# T08-TxClicker-Rev1a.net
KiCad netlist of a schematic drawn in EAGLE
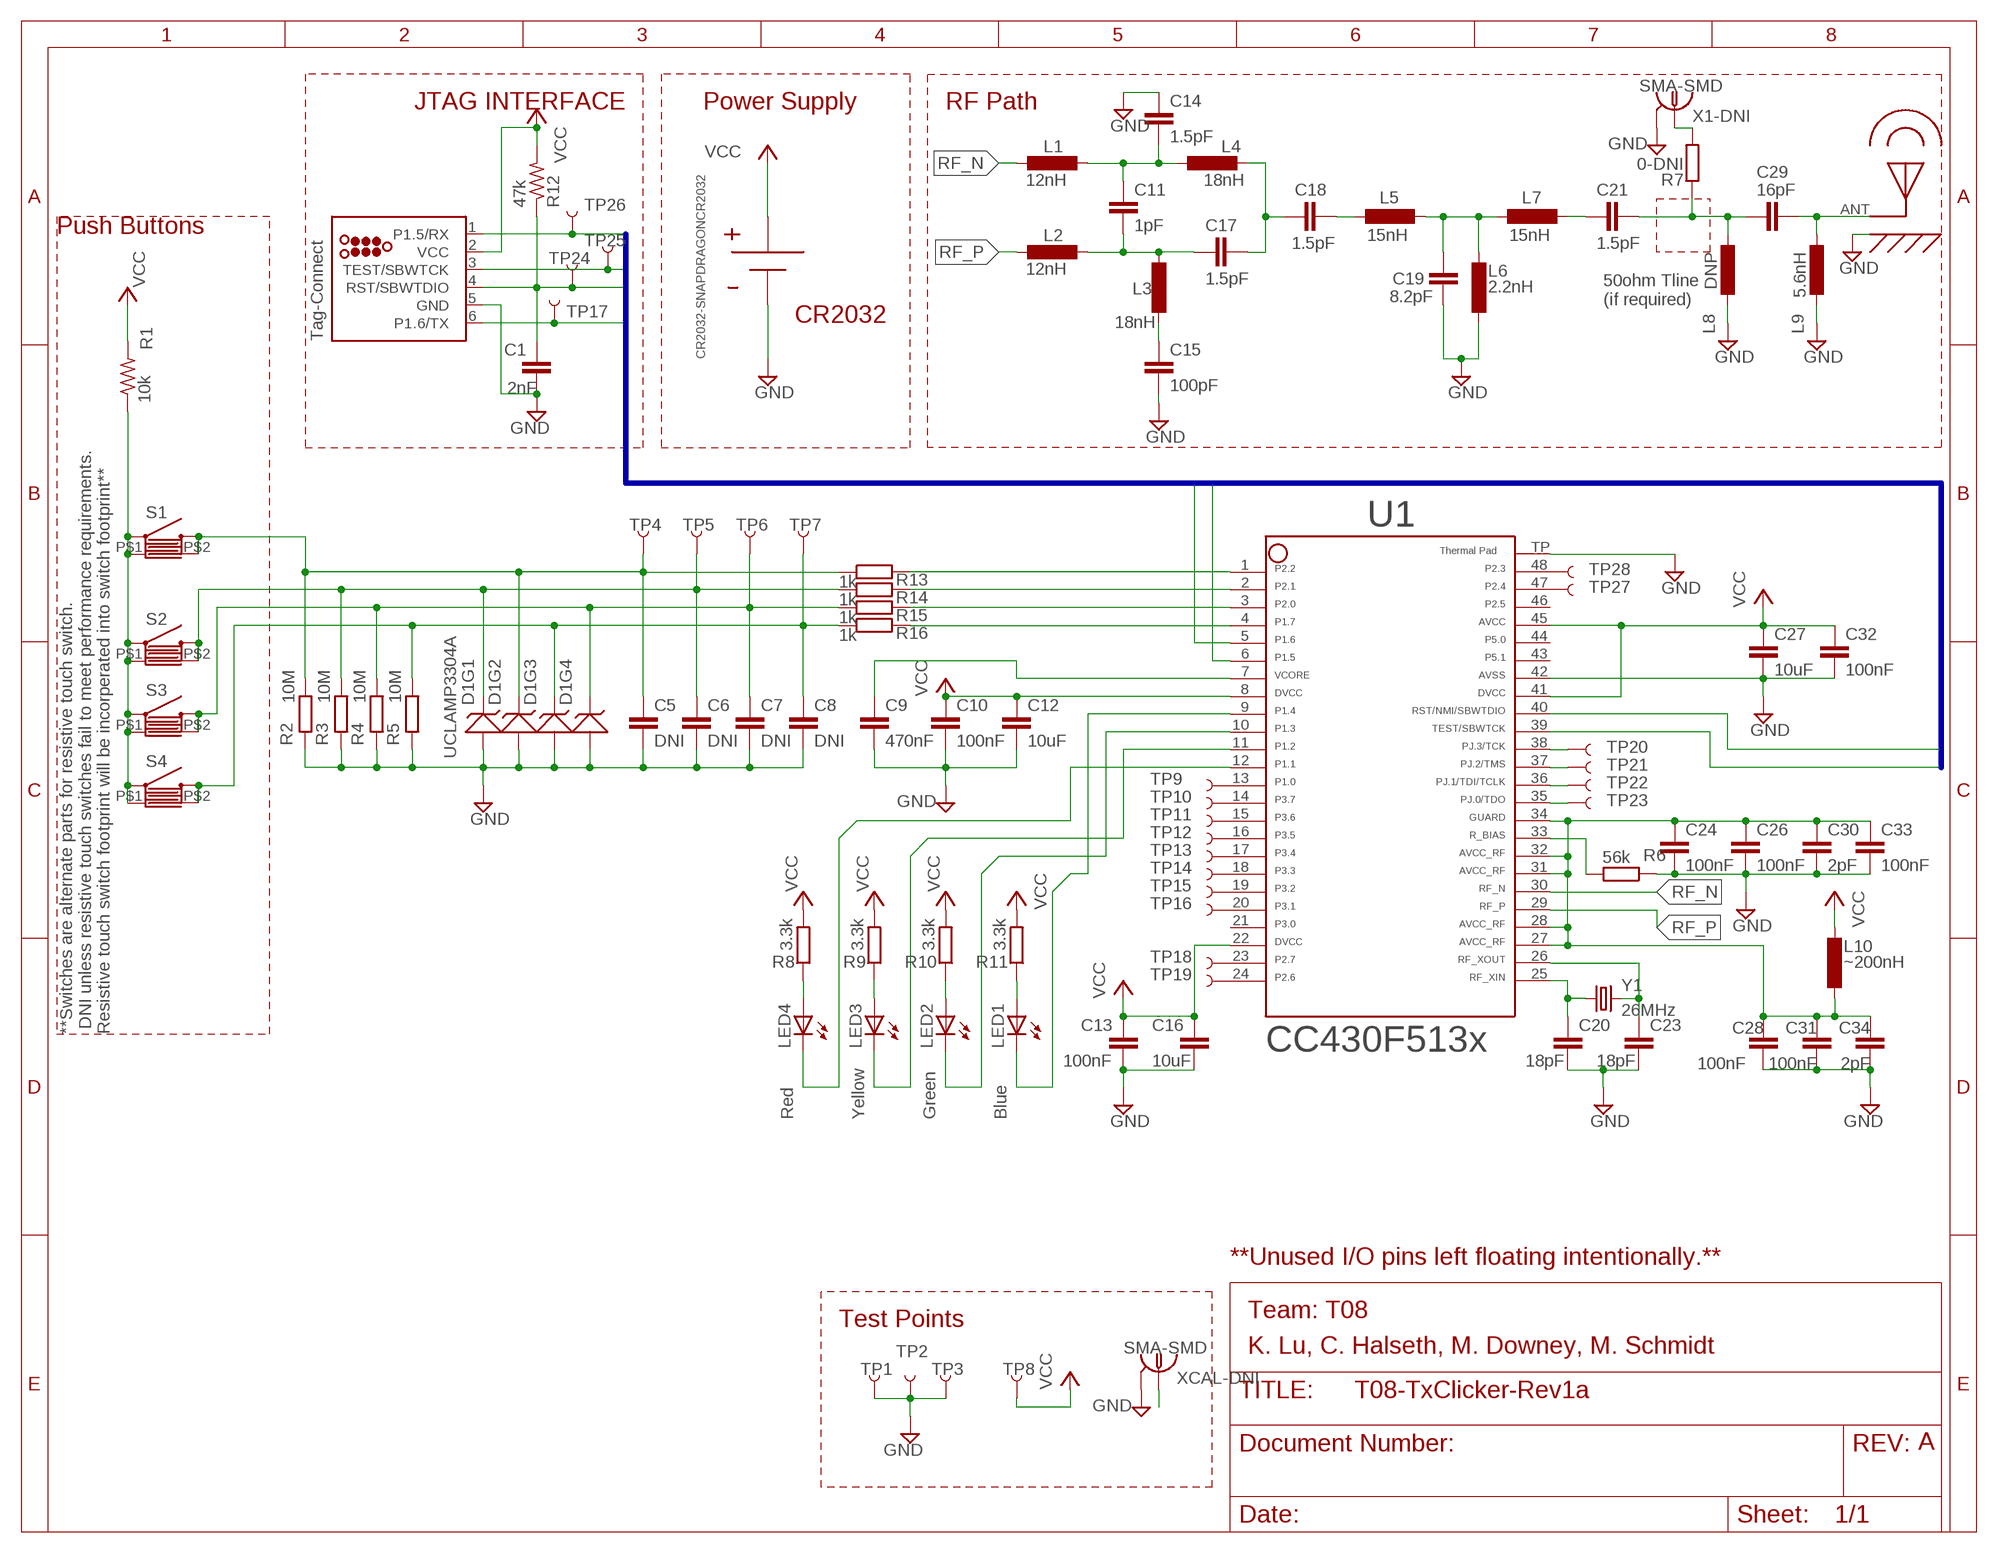
[diagram p0: schematic, sheet 1]

(export (version "E")
  (design (tool "Eeschema 10.0.6"))
  (components
    (comp (ref "C1")
      (value "2nF")
      (footprint "eagle-import:C0603")
      (libsource (lib "eagle-import") (part "C0603"))
    )
    (comp (ref "C5")
      (value "DNI")
      (footprint "eagle-import:C0603")
      (libsource (lib "eagle-import") (part "C0603"))
    )
    (comp (ref "C6")
      (value "DNI")
      (footprint "eagle-import:C0603")
      (libsource (lib "eagle-import") (part "C0603"))
    )
    (comp (ref "C7")
      (value "DNI")
      (footprint "eagle-import:C0603")
      (libsource (lib "eagle-import") (part "C0603"))
    )
    (comp (ref "C8")
      (value "DNI")
      (footprint "eagle-import:C0603")
      (libsource (lib "eagle-import") (part "C0603"))
    )
    (comp (ref "C9")
      (value "470nF")
      (footprint "eagle-import:C0603")
      (libsource (lib "eagle-import") (part "C0603"))
    )
    (comp (ref "C10")
      (value "100nF")
      (footprint "eagle-import:C0603")
      (libsource (lib "eagle-import") (part "C0603"))
    )
    (comp (ref "C11")
      (value "1pF")
      (footprint "eagle-import:C0402")
      (libsource (lib "eagle-import") (part "C0402"))
    )
    (comp (ref "C12")
      (value "10uF")
      (footprint "eagle-import:C0603")
      (libsource (lib "eagle-import") (part "C0603"))
    )
    (comp (ref "C13")
      (value "100nF")
      (footprint "eagle-import:C0603")
      (libsource (lib "eagle-import") (part "C0603"))
    )
    (comp (ref "C14")
      (value "1.5pF")
      (footprint "eagle-import:C0402")
      (libsource (lib "eagle-import") (part "C0402"))
    )
    (comp (ref "C15")
      (value "100pF")
      (footprint "eagle-import:C0402")
      (libsource (lib "eagle-import") (part "C0402"))
    )
    (comp (ref "C16")
      (value "10uF")
      (footprint "eagle-import:C0603")
      (libsource (lib "eagle-import") (part "C0603"))
    )
    (comp (ref "C17")
      (value "1.5pF")
      (footprint "eagle-import:C0402")
      (libsource (lib "eagle-import") (part "C0402"))
    )
    (comp (ref "C18")
      (value "1.5pF")
      (footprint "eagle-import:C0402")
      (libsource (lib "eagle-import") (part "C0402"))
    )
    (comp (ref "C19")
      (value "8.2pF")
      (footprint "eagle-import:C0402")
      (libsource (lib "eagle-import") (part "C0402"))
    )
    (comp (ref "C20")
      (value "18pF")
      (footprint "eagle-import:C0603")
      (libsource (lib "eagle-import") (part "C0603"))
    )
    (comp (ref "C21")
      (value "1.5pF")
      (footprint "eagle-import:C0402")
      (libsource (lib "eagle-import") (part "C0402"))
    )
    (comp (ref "C23")
      (value "18pF")
      (footprint "eagle-import:C0603")
      (libsource (lib "eagle-import") (part "C0603"))
    )
    (comp (ref "C24")
      (value "100nF")
      (footprint "eagle-import:C0603")
      (libsource (lib "eagle-import") (part "C0603"))
    )
    (comp (ref "C26")
      (value "100nF")
      (footprint "eagle-import:C0603")
      (libsource (lib "eagle-import") (part "C0603"))
    )
    (comp (ref "C27")
      (value "10uF")
      (footprint "eagle-import:C0603")
      (libsource (lib "eagle-import") (part "C0603"))
    )
    (comp (ref "C28")
      (value "100nF")
      (footprint "eagle-import:C0603")
      (libsource (lib "eagle-import") (part "C0603"))
    )
    (comp (ref "C29")
      (value "16pF")
      (footprint "eagle-import:C0402")
      (libsource (lib "eagle-import") (part "C0402"))
    )
    (comp (ref "C30")
      (value "2pF")
      (footprint "eagle-import:C0603")
      (libsource (lib "eagle-import") (part "C0603"))
    )
    (comp (ref "C31")
      (value "100nF")
      (footprint "eagle-import:C0603")
      (libsource (lib "eagle-import") (part "C0603"))
    )
    (comp (ref "C32")
      (value "100nF")
      (footprint "eagle-import:C0603")
      (libsource (lib "eagle-import") (part "C0603"))
    )
    (comp (ref "C33")
      (value "100nF")
      (footprint "eagle-import:C0603")
      (libsource (lib "eagle-import") (part "C0603"))
    )
    (comp (ref "C34")
      (value "2pF")
      (footprint "eagle-import:C0603")
      (libsource (lib "eagle-import") (part "C0603"))
    )
    (comp (ref "D1")
      (value "UCLAMP3304A")
      (footprint "eagle-import:SOT666")
      (libsource (lib "eagle-import") (part "UCLAMP3304A"))
    )
    (comp (ref "L1")
      (value "12nH")
      (footprint "eagle-import:L0402")
      (libsource (lib "eagle-import") (part "LL0402"))
    )
    (comp (ref "L2")
      (value "12nH")
      (footprint "eagle-import:L0402")
      (libsource (lib "eagle-import") (part "LL0402"))
    )
    (comp (ref "L3")
      (value "18nH")
      (footprint "eagle-import:L0402")
      (libsource (lib "eagle-import") (part "LL0402"))
    )
    (comp (ref "L4")
      (value "18nH")
      (footprint "eagle-import:L0402")
      (libsource (lib "eagle-import") (part "LL0402"))
    )
    (comp (ref "L5")
      (value "15nH")
      (footprint "eagle-import:L0402")
      (libsource (lib "eagle-import") (part "LL0402"))
    )
    (comp (ref "L6")
      (value "2.2nH")
      (footprint "eagle-import:L0402")
      (libsource (lib "eagle-import") (part "LL0402"))
    )
    (comp (ref "L7")
      (value "15nH")
      (footprint "eagle-import:L0402")
      (libsource (lib "eagle-import") (part "LL0402"))
    )
    (comp (ref "L8")
      (value "DNP")
      (footprint "eagle-import:L0402")
      (libsource (lib "eagle-import") (part "LL0402"))
    )
    (comp (ref "L9")
      (value "5.6nH")
      (footprint "eagle-import:L0402")
      (libsource (lib "eagle-import") (part "LL0402"))
    )
    (comp (ref "L10")
      (value "~200nH")
      (footprint "eagle-import:L0603")
      (libsource (lib "eagle-import") (part "LL0603"))
    )
    (comp (ref "LED1")
      (value "Blue")
      (footprint "eagle-import:CHIP-LED0603")
      (libsource (lib "eagle-import") (part "LEDCHIP-LED0603"))
    )
    (comp (ref "LED2")
      (value "Green")
      (footprint "eagle-import:CHIP-LED0603")
      (libsource (lib "eagle-import") (part "LEDCHIP-LED0603"))
    )
    (comp (ref "LED3")
      (value "Yellow")
      (footprint "eagle-import:CHIP-LED0603")
      (libsource (lib "eagle-import") (part "LEDCHIP-LED0603"))
    )
    (comp (ref "LED4")
      (value "Red")
      (footprint "eagle-import:CHIP-LED0603")
      (libsource (lib "eagle-import") (part "LEDCHIP-LED0603"))
    )
    (comp (ref "R1")
      (value "10k")
      (footprint "eagle-import:R0603")
      (libsource (lib "eagle-import") (part "R-US_R0603"))
    )
    (comp (ref "R2")
      (value "10M")
      (footprint "eagle-import:R0603")
      (libsource (lib "eagle-import") (part "R0603"))
    )
    (comp (ref "R3")
      (value "10M")
      (footprint "eagle-import:R0603")
      (libsource (lib "eagle-import") (part "R0603"))
    )
    (comp (ref "R4")
      (value "10M")
      (footprint "eagle-import:R0603")
      (libsource (lib "eagle-import") (part "R0603"))
    )
    (comp (ref "R5")
      (value "10M")
      (footprint "eagle-import:R0603")
      (libsource (lib "eagle-import") (part "R0603"))
    )
    (comp (ref "R6")
      (value "56k")
      (footprint "eagle-import:R0603")
      (libsource (lib "eagle-import") (part "R0603"))
    )
    (comp (ref "R7")
      (value "0-DNI")
      (footprint "eagle-import:R0603")
      (libsource (lib "eagle-import") (part "R0603"))
    )
    (comp (ref "R8")
      (value "3.3k")
      (footprint "eagle-import:R0603")
      (libsource (lib "eagle-import") (part "R0603"))
    )
    (comp (ref "R9")
      (value "3.3k")
      (footprint "eagle-import:R0603")
      (libsource (lib "eagle-import") (part "R0603"))
    )
    (comp (ref "R10")
      (value "3.3k")
      (footprint "eagle-import:R0603")
      (libsource (lib "eagle-import") (part "R0603"))
    )
    (comp (ref "R11")
      (value "3.3k")
      (footprint "eagle-import:R0603")
      (libsource (lib "eagle-import") (part "R0603"))
    )
    (comp (ref "R12")
      (value "47k")
      (footprint "eagle-import:R0603")
      (libsource (lib "eagle-import") (part "R-US_R0603"))
    )
    (comp (ref "R13")
      (value "1k")
      (footprint "eagle-import:R0603")
      (libsource (lib "eagle-import") (part "R0603"))
    )
    (comp (ref "R14")
      (value "1k")
      (footprint "eagle-import:R0603")
      (libsource (lib "eagle-import") (part "R0603"))
    )
    (comp (ref "R15")
      (value "1k")
      (footprint "eagle-import:R0603")
      (libsource (lib "eagle-import") (part "R0603"))
    )
    (comp (ref "R16")
      (value "1k")
      (footprint "eagle-import:R0603")
      (libsource (lib "eagle-import") (part "R0603"))
    )
    (comp (ref "S1")
      (value "TOUCHPAD_SWITCH_COMBOSWITC_TOUCHPAD")
      (footprint "eagle-import:TACTILE-PTH-12MM")
      (libsource (lib "eagle-import") (part "TOUCHPAD_SWITCH_COMBOSWITC_TOUCHPAD"))
    )
    (comp (ref "S2")
      (value "TOUCHPAD_SWITCH_COMBOSWITC_TOUCHPAD")
      (footprint "eagle-import:TACTILE-PTH-12MM")
      (libsource (lib "eagle-import") (part "TOUCHPAD_SWITCH_COMBOSWITC_TOUCHPAD"))
    )
    (comp (ref "S3")
      (value "TOUCHPAD_SWITCH_COMBOSWITC_TOUCHPAD")
      (footprint "eagle-import:TACTILE-PTH-12MM")
      (libsource (lib "eagle-import") (part "TOUCHPAD_SWITCH_COMBOSWITC_TOUCHPAD"))
    )
    (comp (ref "S4")
      (value "TOUCHPAD_SWITCH_COMBOSWITC_TOUCHPAD")
      (footprint "eagle-import:TACTILE-PTH-12MM")
      (libsource (lib "eagle-import") (part "TOUCHPAD_SWITCH_COMBOSWITC_TOUCHPAD"))
    )
    (comp (ref "TP1")
      (value "TEST-POINT3")
      (footprint "eagle-import:PAD.03X.03")
      (libsource (lib "eagle-import") (part "TEST-POINT3"))
    )
    (comp (ref "TP2")
      (value "TEST-POINT3")
      (footprint "eagle-import:PAD.03X.03")
      (libsource (lib "eagle-import") (part "TEST-POINT3"))
    )
    (comp (ref "TP3")
      (value "TEST-POINT3")
      (footprint "eagle-import:PAD.03X.03")
      (libsource (lib "eagle-import") (part "TEST-POINT3"))
    )
    (comp (ref "TP4")
      (value "TEST-POINT3")
      (footprint "eagle-import:PAD.03X.03")
      (libsource (lib "eagle-import") (part "TEST-POINT3"))
    )
    (comp (ref "TP5")
      (value "TEST-POINT3")
      (footprint "eagle-import:PAD.03X.03")
      (libsource (lib "eagle-import") (part "TEST-POINT3"))
    )
    (comp (ref "TP6")
      (value "TEST-POINT3")
      (footprint "eagle-import:PAD.03X.03")
      (libsource (lib "eagle-import") (part "TEST-POINT3"))
    )
    (comp (ref "TP7")
      (value "TEST-POINT3")
      (footprint "eagle-import:PAD.03X.03")
      (libsource (lib "eagle-import") (part "TEST-POINT3"))
    )
    (comp (ref "TP8")
      (value "TEST-POINT3")
      (footprint "eagle-import:PAD.03X.03")
      (libsource (lib "eagle-import") (part "TEST-POINT3"))
    )
    (comp (ref "TP9")
      (value "TP9")
      (footprint "eagle-import:PAD.03X.03")
      (libsource (lib "eagle-import") (part "TEST-POINT3"))
    )
    (comp (ref "TP10")
      (value "TEST-POINT3")
      (footprint "eagle-import:PAD.03X.03")
      (libsource (lib "eagle-import") (part "TEST-POINT3"))
    )
    (comp (ref "TP11")
      (value "TEST-POINT3")
      (footprint "eagle-import:PAD.03X.03")
      (libsource (lib "eagle-import") (part "TEST-POINT3"))
    )
    (comp (ref "TP12")
      (value "TEST-POINT3")
      (footprint "eagle-import:PAD.03X.03")
      (libsource (lib "eagle-import") (part "TEST-POINT3"))
    )
    (comp (ref "TP13")
      (value "TEST-POINT3")
      (footprint "eagle-import:PAD.03X.03")
      (libsource (lib "eagle-import") (part "TEST-POINT3"))
    )
    (comp (ref "TP14")
      (value "TEST-POINT3")
      (footprint "eagle-import:PAD.03X.03")
      (libsource (lib "eagle-import") (part "TEST-POINT3"))
    )
    (comp (ref "TP15")
      (value "TEST-POINT3")
      (footprint "eagle-import:PAD.03X.03")
      (libsource (lib "eagle-import") (part "TEST-POINT3"))
    )
    (comp (ref "TP16")
      (value "TEST-POINT3")
      (footprint "eagle-import:PAD.03X.03")
      (libsource (lib "eagle-import") (part "TEST-POINT3"))
    )
    (comp (ref "TP17")
      (value "TEST-POINT3")
      (footprint "eagle-import:PAD.03X.03")
      (libsource (lib "eagle-import") (part "TEST-POINT3"))
    )
    (comp (ref "TP18")
      (value "TEST-POINT3")
      (footprint "eagle-import:PAD.03X.03")
      (libsource (lib "eagle-import") (part "TEST-POINT3"))
    )
    (comp (ref "TP19")
      (value "TEST-POINT3")
      (footprint "eagle-import:PAD.03X.03")
      (libsource (lib "eagle-import") (part "TEST-POINT3"))
    )
    (comp (ref "TP20")
      (value "TEST-POINT3")
      (footprint "eagle-import:PAD.03X.03")
      (libsource (lib "eagle-import") (part "TEST-POINT3"))
    )
    (comp (ref "TP21")
      (value "TEST-POINT3")
      (footprint "eagle-import:PAD.03X.03")
      (libsource (lib "eagle-import") (part "TEST-POINT3"))
    )
    (comp (ref "TP22")
      (value "TEST-POINT3")
      (footprint "eagle-import:PAD.03X.03")
      (libsource (lib "eagle-import") (part "TEST-POINT3"))
    )
    (comp (ref "TP23")
      (value "TEST-POINT3")
      (footprint "eagle-import:PAD.03X.03")
      (libsource (lib "eagle-import") (part "TEST-POINT3"))
    )
    (comp (ref "TP24")
      (value "TEST-POINT3")
      (footprint "eagle-import:PAD.03X.03")
      (libsource (lib "eagle-import") (part "TEST-POINT3"))
    )
    (comp (ref "TP25")
      (value "TEST-POINT3")
      (footprint "eagle-import:PAD.03X.03")
      (libsource (lib "eagle-import") (part "TEST-POINT3"))
    )
    (comp (ref "TP26")
      (value "TEST-POINT3")
      (footprint "eagle-import:PAD.03X.03")
      (libsource (lib "eagle-import") (part "TEST-POINT3"))
    )
    (comp (ref "TP27")
      (value "TEST-POINT3")
      (footprint "eagle-import:PAD.03X.03")
      (libsource (lib "eagle-import") (part "TEST-POINT3"))
    )
    (comp (ref "TP28")
      (value "TEST-POINT3")
      (footprint "eagle-import:PAD.03X.03")
      (libsource (lib "eagle-import") (part "TEST-POINT3"))
    )
    (comp (ref "U$1")
      (value "TC2030-MCP")
      (footprint "eagle-import:TC2030-MCP")
      (libsource (lib "eagle-import") (part "TC2030-MCP"))
    )
    (comp (ref "U$5")
      (value "CR2032-SNAPDRAGONCR2032")
      (footprint "eagle-import:CR2032-SNAPDRAGON")
      (libsource (lib "eagle-import") (part "CR2032-SNAPDRAGONCR2032"))
    )
    (comp (ref "U$6")
      (value "PCB_ANTENNA_915MHZOSHP")
      (footprint "eagle-import:PCB_ANTENNA_915MHZ")
      (libsource (lib "eagle-import") (part "PCB_ANTENNA_915MHZOSHP"))
    )
    (comp (ref "U1")
      (value "CC430F513X---RGZ48")
      (footprint "eagle-import:RGZ48")
      (libsource (lib "eagle-import") (part "CC430F513X---RGZ48"))
    )
    (comp (ref "X1-DNI")
      (value "SMA-SMD")
      (footprint "eagle-import:SMA-SMD")
      (libsource (lib "eagle-import") (part "SMA-SMD"))
    )
    (comp (ref "XCAL-DNI")
      (value "SMA-SMD")
      (footprint "eagle-import:SMA-SMD")
      (libsource (lib "eagle-import") (part "SMA-SMD"))
    )
    (comp (ref "Y1")
      (value "26MHz")
      (footprint "eagle-import:CRYSTAL-TXC-7A")
      (libsource (lib "eagle-import") (part "CRYSTALTXC-7A"))
    )
  )
  (nets
    (net (code "1") (name "/P1.5{slash}RX") (class "Default")
      (node (ref "TP26") (pin "P$1") (pinfunction "1_P$1") (pintype "bidirectional"))
      (node (ref "U$1") (pin "1") (pinfunction "P1.5/RX_1") (pintype "bidirectional"))
      (node (ref "U1") (pin "6") (pinfunction "6_6") (pintype "bidirectional"))
    )
    (net (code "2") (name "/P1.6{slash}TX") (class "Default")
      (node (ref "TP17") (pin "P$1") (pinfunction "1_P$1") (pintype "bidirectional"))
      (node (ref "U$1") (pin "6") (pinfunction "P1.6/TX_6") (pintype "bidirectional"))
      (node (ref "U1") (pin "5") (pinfunction "5_5") (pintype "bidirectional"))
    )
    (net (code "3") (name "/RST{slash}NMI{slash}SBWTDIO") (class "Default")
      (node (ref "C1") (pin "1") (pinfunction "1_1") (pintype "passive"))
      (node (ref "R12") (pin "1") (pinfunction "1_1") (pintype "passive"))
      (node (ref "TP24") (pin "P$1") (pinfunction "1_P$1") (pintype "bidirectional"))
      (node (ref "U$1") (pin "4") (pinfunction "RST/SBWTDIO_4") (pintype "bidirectional"))
      (node (ref "U1") (pin "40") (pinfunction "40_40") (pintype "bidirectional"))
    )
    (net (code "4") (name "/TEST{slash}SBWTCK") (class "Default")
      (node (ref "TP25") (pin "P$1") (pinfunction "1_P$1") (pintype "bidirectional"))
      (node (ref "U$1") (pin "3") (pinfunction "TEST/SBWTCK_3") (pintype "bidirectional"))
      (node (ref "U1") (pin "39") (pinfunction "39_39") (pintype "input"))
    )
    (net (code "5") (name "GND") (class "Default")
      (node (ref "C1") (pin "2") (pinfunction "2_2") (pintype "passive"))
      (node (ref "C10") (pin "2") (pinfunction "2_2") (pintype "passive"))
      (node (ref "C12") (pin "2") (pinfunction "2_2") (pintype "passive"))
      (node (ref "C13") (pin "2") (pinfunction "2_2") (pintype "passive"))
      (node (ref "C14") (pin "P$1") (pinfunction "1_P$1") (pintype "passive"))
      (node (ref "C15") (pin "P$2") (pinfunction "2_P$2") (pintype "passive"))
      (node (ref "C16") (pin "2") (pinfunction "2_2") (pintype "passive"))
      (node (ref "C19") (pin "P$1") (pinfunction "1_P$1") (pintype "passive"))
      (node (ref "C20") (pin "2") (pinfunction "2_2") (pintype "passive"))
      (node (ref "C23") (pin "2") (pinfunction "2_2") (pintype "passive"))
      (node (ref "C24") (pin "2") (pinfunction "2_2") (pintype "passive"))
      (node (ref "C26") (pin "2") (pinfunction "2_2") (pintype "passive"))
      (node (ref "C27") (pin "2") (pinfunction "2_2") (pintype "passive"))
      (node (ref "C28") (pin "2") (pinfunction "2_2") (pintype "passive"))
      (node (ref "C30") (pin "2") (pinfunction "2_2") (pintype "passive"))
      (node (ref "C31") (pin "2") (pinfunction "2_2") (pintype "passive"))
      (node (ref "C32") (pin "2") (pinfunction "2_2") (pintype "passive"))
      (node (ref "C33") (pin "2") (pinfunction "2_2") (pintype "passive"))
      (node (ref "C34") (pin "2") (pinfunction "2_2") (pintype "passive"))
      (node (ref "C5") (pin "2") (pinfunction "2_2") (pintype "passive"))
      (node (ref "C6") (pin "2") (pinfunction "2_2") (pintype "passive"))
      (node (ref "C7") (pin "2") (pinfunction "2_2") (pintype "passive"))
      (node (ref "C8") (pin "2") (pinfunction "2_2") (pintype "passive"))
      (node (ref "C9") (pin "2") (pinfunction "2_2") (pintype "passive"))
      (node (ref "D1") (pin "2") (pinfunction "2_2") (pintype "bidirectional"))
      (node (ref "D1") (pin "5") (pinfunction "2_5") (pintype "bidirectional"))
      (node (ref "L6") (pin "P$2") (pinfunction "2_P$2") (pintype "passive"))
      (node (ref "L8") (pin "P$1") (pinfunction "1_P$1") (pintype "passive"))
      (node (ref "L9") (pin "P$1") (pinfunction "1_P$1") (pintype "passive"))
      (node (ref "R2") (pin "1") (pinfunction "1_1") (pintype "passive"))
      (node (ref "R3") (pin "1") (pinfunction "1_1") (pintype "passive"))
      (node (ref "R4") (pin "1") (pinfunction "1_1") (pintype "passive"))
      (node (ref "R5") (pin "1") (pinfunction "1_1") (pintype "passive"))
      (node (ref "R6") (pin "1") (pinfunction "1_1") (pintype "passive"))
      (node (ref "TP1") (pin "P$1") (pinfunction "1_P$1") (pintype "bidirectional"))
      (node (ref "TP2") (pin "P$1") (pinfunction "1_P$1") (pintype "bidirectional"))
      (node (ref "TP3") (pin "P$1") (pinfunction "1_P$1") (pintype "bidirectional"))
      (node (ref "U$1") (pin "5") (pinfunction "GND_5") (pintype "power_in"))
      (node (ref "U$5") (pin "V-") (pinfunction "V-_V-") (pintype "bidirectional"))
      (node (ref "U$6") (pin "GPLANE") (pinfunction "GND_GPLANE") (pintype "power_in"))
      (node (ref "U1") (pin "42") (pinfunction "42_42") (pintype "power_in"))
      (node (ref "U1") (pin "TP") (pinfunction "49_TP") (pintype "power_in"))
      (node (ref "X1-DNI") (pin "2@1") (pinfunction "2_2@1") (pintype "passive"))
      (node (ref "X1-DNI") (pin "2@2") (pinfunction "2_2@2") (pintype "passive"))
      (node (ref "X1-DNI") (pin "2@3") (pinfunction "2_2@3") (pintype "passive"))
      (node (ref "X1-DNI") (pin "2@4") (pinfunction "2_2@4") (pintype "passive"))
      (node (ref "X1-DNI") (pin "2@5") (pinfunction "2_2@5") (pintype "passive"))
      (node (ref "X1-DNI") (pin "2@6") (pinfunction "2_2@6") (pintype "passive"))
      (node (ref "XCAL-DNI") (pin "2@1") (pinfunction "2_2@1") (pintype "passive"))
      (node (ref "XCAL-DNI") (pin "2@2") (pinfunction "2_2@2") (pintype "passive"))
      (node (ref "XCAL-DNI") (pin "2@3") (pinfunction "2_2@3") (pintype "passive"))
      (node (ref "XCAL-DNI") (pin "2@4") (pinfunction "2_2@4") (pintype "passive"))
      (node (ref "XCAL-DNI") (pin "2@5") (pinfunction "2_2@5") (pintype "passive"))
      (node (ref "XCAL-DNI") (pin "2@6") (pinfunction "2_2@6") (pintype "passive"))
    )
    (net (code "6") (name "Net-(C9-Pad1)") (class "Default")
      (node (ref "C9") (pin "1") (pinfunction "1_1") (pintype "passive"))
      (node (ref "U1") (pin "7") (pinfunction "7_7") (pintype "power_in"))
    )
    (net (code "7") (name "Net-(C11-1)") (class "Default")
      (node (ref "C11") (pin "P$1") (pinfunction "1_P$1") (pintype "passive"))
      (node (ref "C14") (pin "P$2") (pinfunction "2_P$2") (pintype "passive"))
      (node (ref "L1") (pin "P$1") (pinfunction "1_P$1") (pintype "passive"))
      (node (ref "L4") (pin "P$2") (pinfunction "2_P$2") (pintype "passive"))
    )
    (net (code "8") (name "Net-(C11-2)") (class "Default")
      (node (ref "C11") (pin "P$2") (pinfunction "2_P$2") (pintype "passive"))
      (node (ref "C17") (pin "P$2") (pinfunction "2_P$2") (pintype "passive"))
      (node (ref "L2") (pin "P$1") (pinfunction "1_P$1") (pintype "passive"))
      (node (ref "L3") (pin "P$1") (pinfunction "1_P$1") (pintype "passive"))
    )
    (net (code "9") (name "Net-(C15-1)") (class "Default")
      (node (ref "C15") (pin "P$1") (pinfunction "1_P$1") (pintype "passive"))
      (node (ref "L3") (pin "P$2") (pinfunction "2_P$2") (pintype "passive"))
    )
    (net (code "10") (name "Net-(C17-1)") (class "Default")
      (node (ref "C17") (pin "P$1") (pinfunction "1_P$1") (pintype "passive"))
      (node (ref "C18") (pin "P$1") (pinfunction "1_P$1") (pintype "passive"))
      (node (ref "L4") (pin "P$1") (pinfunction "1_P$1") (pintype "passive"))
    )
    (net (code "11") (name "Net-(C18-2)") (class "Default")
      (node (ref "C18") (pin "P$2") (pinfunction "2_P$2") (pintype "passive"))
      (node (ref "L5") (pin "P$1") (pinfunction "1_P$1") (pintype "passive"))
    )
    (net (code "12") (name "Net-(C19-2)") (class "Default")
      (node (ref "C19") (pin "P$2") (pinfunction "2_P$2") (pintype "passive"))
      (node (ref "L5") (pin "P$2") (pinfunction "2_P$2") (pintype "passive"))
      (node (ref "L6") (pin "P$1") (pinfunction "1_P$1") (pintype "passive"))
      (node (ref "L7") (pin "P$1") (pinfunction "1_P$1") (pintype "passive"))
    )
    (net (code "13") (name "Net-(C21-1)") (class "Default")
      (node (ref "C21") (pin "P$1") (pinfunction "1_P$1") (pintype "passive"))
      (node (ref "C29") (pin "P$2") (pinfunction "2_P$2") (pintype "passive"))
      (node (ref "L8") (pin "P$2") (pinfunction "2_P$2") (pintype "passive"))
      (node (ref "R7") (pin "1") (pinfunction "1_1") (pintype "passive"))
    )
    (net (code "14") (name "Net-(C21-2)") (class "Default")
      (node (ref "C21") (pin "P$2") (pinfunction "2_P$2") (pintype "passive"))
      (node (ref "L7") (pin "P$2") (pinfunction "2_P$2") (pintype "passive"))
    )
    (net (code "15") (name "Net-(C24-Pad1)") (class "Default")
      (node (ref "C24") (pin "1") (pinfunction "1_1") (pintype "passive"))
      (node (ref "C26") (pin "1") (pinfunction "1_1") (pintype "passive"))
      (node (ref "C28") (pin "1") (pinfunction "1_1") (pintype "passive"))
      (node (ref "C30") (pin "1") (pinfunction "1_1") (pintype "passive"))
      (node (ref "C31") (pin "1") (pinfunction "1_1") (pintype "passive"))
      (node (ref "C33") (pin "1") (pinfunction "1_1") (pintype "passive"))
      (node (ref "C34") (pin "1") (pinfunction "1_1") (pintype "passive"))
      (node (ref "L10") (pin "2") (pinfunction "2_2") (pintype "passive"))
      (node (ref "U1") (pin "27") (pinfunction "27_27") (pintype "power_in"))
      (node (ref "U1") (pin "28") (pinfunction "28_28") (pintype "bidirectional"))
      (node (ref "U1") (pin "31") (pinfunction "31_31") (pintype "power_in"))
      (node (ref "U1") (pin "32") (pinfunction "32_32") (pintype "power_in"))
      (node (ref "U1") (pin "34") (pinfunction "34_34") (pintype "power_in"))
    )
    (net (code "16") (name "Net-(C29-1)") (class "Default")
      (node (ref "C29") (pin "P$1") (pinfunction "1_P$1") (pintype "passive"))
      (node (ref "L9") (pin "P$2") (pinfunction "2_P$2") (pintype "passive"))
      (node (ref "U$6") (pin "ANT") (pinfunction "ANT_ANT") (pintype "input"))
    )
    (net (code "17") (name "Net-(D1B-1)") (class "Default")
      (node (ref "C5") (pin "1") (pinfunction "1_1") (pintype "passive"))
      (node (ref "D1") (pin "3") (pinfunction "1_3") (pintype "bidirectional"))
      (node (ref "R13") (pin "1") (pinfunction "1_1") (pintype "passive"))
      (node (ref "R2") (pin "2") (pinfunction "2_2") (pintype "passive"))
      (node (ref "S1") (pin "3") (pinfunction "TOP_3") (pintype "passive"))
      (node (ref "S1") (pin "P$2") (pinfunction "TOP_P$2") (pintype "passive"))
      (node (ref "TP4") (pin "P$1") (pinfunction "1_P$1") (pintype "bidirectional"))
    )
    (net (code "18") (name "Net-(D1C-P$1)") (class "Default")
      (node (ref "C8") (pin "1") (pinfunction "1_1") (pintype "passive"))
      (node (ref "D1") (pin "4") (pinfunction "P$1_4") (pintype "bidirectional"))
      (node (ref "R16") (pin "1") (pinfunction "1_1") (pintype "passive"))
      (node (ref "R5") (pin "2") (pinfunction "2_2") (pintype "passive"))
      (node (ref "S4") (pin "3") (pinfunction "TOP_3") (pintype "passive"))
      (node (ref "S4") (pin "P$2") (pinfunction "TOP_P$2") (pintype "passive"))
      (node (ref "TP7") (pin "P$1") (pinfunction "1_P$1") (pintype "bidirectional"))
    )
    (net (code "19") (name "Net-(D1D-P$1)") (class "Default")
      (node (ref "C7") (pin "1") (pinfunction "1_1") (pintype "passive"))
      (node (ref "D1") (pin "6") (pinfunction "P$1_6") (pintype "bidirectional"))
      (node (ref "R15") (pin "1") (pinfunction "1_1") (pintype "passive"))
      (node (ref "R4") (pin "2") (pinfunction "2_2") (pintype "passive"))
      (node (ref "S3") (pin "3") (pinfunction "TOP_3") (pintype "passive"))
      (node (ref "S3") (pin "P$2") (pinfunction "TOP_P$2") (pintype "passive"))
      (node (ref "TP6") (pin "P$1") (pinfunction "1_P$1") (pintype "bidirectional"))
    )
    (net (code "20") (name "Net-(LED1-PadA)") (class "Default")
      (node (ref "LED1") (pin "A") (pinfunction "A_A") (pintype "bidirectional"))
      (node (ref "R11") (pin "1") (pinfunction "1_1") (pintype "passive"))
    )
    (net (code "21") (name "Net-(LED1-PadC)") (class "Default")
      (node (ref "LED1") (pin "C") (pinfunction "C_C") (pintype "bidirectional"))
      (node (ref "U1") (pin "9") (pinfunction "9_9") (pintype "bidirectional"))
    )
    (net (code "22") (name "Net-(LED2-PadA)") (class "Default")
      (node (ref "LED2") (pin "A") (pinfunction "A_A") (pintype "bidirectional"))
      (node (ref "R10") (pin "1") (pinfunction "1_1") (pintype "passive"))
    )
    (net (code "23") (name "Net-(LED2-PadC)") (class "Default")
      (node (ref "LED2") (pin "C") (pinfunction "C_C") (pintype "bidirectional"))
      (node (ref "U1") (pin "10") (pinfunction "10_10") (pintype "bidirectional"))
    )
    (net (code "24") (name "Net-(LED3-PadA)") (class "Default")
      (node (ref "LED3") (pin "A") (pinfunction "A_A") (pintype "bidirectional"))
      (node (ref "R9") (pin "1") (pinfunction "1_1") (pintype "passive"))
    )
    (net (code "25") (name "Net-(LED3-PadC)") (class "Default")
      (node (ref "LED3") (pin "C") (pinfunction "C_C") (pintype "bidirectional"))
      (node (ref "U1") (pin "11") (pinfunction "11_11") (pintype "bidirectional"))
    )
    (net (code "26") (name "Net-(LED4-PadA)") (class "Default")
      (node (ref "LED4") (pin "A") (pinfunction "A_A") (pintype "bidirectional"))
      (node (ref "R8") (pin "1") (pinfunction "1_1") (pintype "passive"))
    )
    (net (code "27") (name "Net-(LED4-PadC)") (class "Default")
      (node (ref "LED4") (pin "C") (pinfunction "C_C") (pintype "bidirectional"))
      (node (ref "U1") (pin "12") (pinfunction "12_12") (pintype "bidirectional"))
    )
    (net (code "28") (name "Net-(R1-Pad1)") (class "Default")
      (node (ref "R1") (pin "1") (pinfunction "1_1") (pintype "passive"))
      (node (ref "S1") (pin "1") (pinfunction "BASE_1") (pintype "passive"))
      (node (ref "S1") (pin "P$1") (pinfunction "BASE_P$1") (pintype "passive"))
      (node (ref "S2") (pin "1") (pinfunction "BASE_1") (pintype "passive"))
      (node (ref "S2") (pin "P$1") (pinfunction "BASE_P$1") (pintype "passive"))
      (node (ref "S3") (pin "1") (pinfunction "BASE_1") (pintype "passive"))
      (node (ref "S3") (pin "P$1") (pinfunction "BASE_P$1") (pintype "passive"))
      (node (ref "S4") (pin "1") (pinfunction "BASE_1") (pintype "passive"))
      (node (ref "S4") (pin "P$1") (pinfunction "BASE_P$1") (pintype "passive"))
    )
    (net (code "29") (name "Net-(R6-Pad2)") (class "Default")
      (node (ref "R6") (pin "2") (pinfunction "2_2") (pintype "passive"))
      (node (ref "U1") (pin "33") (pinfunction "33_33") (pintype "power_in"))
    )
    (net (code "30") (name "Net-(R7-Pad2)") (class "Default")
      (node (ref "R7") (pin "2") (pinfunction "2_2") (pintype "passive"))
      (node (ref "X1-DNI") (pin "1") (pinfunction "1_1") (pintype "passive"))
    )
    (net (code "31") (name "Net-(R13-Pad2)") (class "Default")
      (node (ref "R13") (pin "2") (pinfunction "2_2") (pintype "passive"))
      (node (ref "U1") (pin "1") (pinfunction "1_1") (pintype "bidirectional"))
    )
    (net (code "32") (name "Net-(R14-Pad2)") (class "Default")
      (node (ref "R14") (pin "2") (pinfunction "2_2") (pintype "passive"))
      (node (ref "U1") (pin "2") (pinfunction "2_2") (pintype "bidirectional"))
    )
    (net (code "33") (name "Net-(R15-Pad2)") (class "Default")
      (node (ref "R15") (pin "2") (pinfunction "2_2") (pintype "passive"))
      (node (ref "U1") (pin "3") (pinfunction "3_3") (pintype "bidirectional"))
    )
    (net (code "34") (name "Net-(R16-Pad2)") (class "Default")
      (node (ref "R16") (pin "2") (pinfunction "2_2") (pintype "passive"))
      (node (ref "U1") (pin "4") (pinfunction "4_4") (pintype "bidirectional"))
    )
    (net (code "35") (name "Net-(TP5-1)") (class "Default")
      (node (ref "C6") (pin "1") (pinfunction "1_1") (pintype "passive"))
      (node (ref "D1") (pin "1") (pinfunction "1_1") (pintype "bidirectional"))
      (node (ref "R14") (pin "1") (pinfunction "1_1") (pintype "passive"))
      (node (ref "R3") (pin "2") (pinfunction "2_2") (pintype "passive"))
      (node (ref "S2") (pin "3") (pinfunction "TOP_3") (pintype "passive"))
      (node (ref "S2") (pin "P$2") (pinfunction "TOP_P$2") (pintype "passive"))
      (node (ref "TP5") (pin "P$1") (pinfunction "1_P$1") (pintype "bidirectional"))
    )
    (net (code "36") (name "Net-(TP9-1)") (class "Default")
      (node (ref "TP9") (pin "P$1") (pinfunction "1_P$1") (pintype "bidirectional"))
      (node (ref "U1") (pin "13") (pinfunction "13_13") (pintype "bidirectional"))
    )
    (net (code "37") (name "Net-(TP10-1)") (class "Default")
      (node (ref "TP10") (pin "P$1") (pinfunction "1_P$1") (pintype "bidirectional"))
      (node (ref "U1") (pin "14") (pinfunction "14_14") (pintype "bidirectional"))
    )
    (net (code "38") (name "Net-(TP11-1)") (class "Default")
      (node (ref "TP11") (pin "P$1") (pinfunction "1_P$1") (pintype "bidirectional"))
      (node (ref "U1") (pin "15") (pinfunction "15_15") (pintype "bidirectional"))
    )
    (net (code "39") (name "Net-(TP12-1)") (class "Default")
      (node (ref "TP12") (pin "P$1") (pinfunction "1_P$1") (pintype "bidirectional"))
      (node (ref "U1") (pin "16") (pinfunction "16_16") (pintype "bidirectional"))
    )
    (net (code "40") (name "Net-(TP13-1)") (class "Default")
      (node (ref "TP13") (pin "P$1") (pinfunction "1_P$1") (pintype "bidirectional"))
      (node (ref "U1") (pin "17") (pinfunction "17_17") (pintype "bidirectional"))
    )
    (net (code "41") (name "Net-(TP14-1)") (class "Default")
      (node (ref "TP14") (pin "P$1") (pinfunction "1_P$1") (pintype "bidirectional"))
      (node (ref "U1") (pin "18") (pinfunction "18_18") (pintype "bidirectional"))
    )
    (net (code "42") (name "Net-(TP15-1)") (class "Default")
      (node (ref "TP15") (pin "P$1") (pinfunction "1_P$1") (pintype "bidirectional"))
      (node (ref "U1") (pin "19") (pinfunction "19_19") (pintype "bidirectional"))
    )
    (net (code "43") (name "Net-(TP16-1)") (class "Default")
      (node (ref "TP16") (pin "P$1") (pinfunction "1_P$1") (pintype "bidirectional"))
      (node (ref "U1") (pin "20") (pinfunction "20_20") (pintype "bidirectional"))
    )
    (net (code "44") (name "Net-(TP18-1)") (class "Default")
      (node (ref "TP18") (pin "P$1") (pinfunction "1_P$1") (pintype "bidirectional"))
      (node (ref "U1") (pin "23") (pinfunction "23_23") (pintype "bidirectional"))
    )
    (net (code "45") (name "Net-(TP19-1)") (class "Default")
      (node (ref "TP19") (pin "P$1") (pinfunction "1_P$1") (pintype "bidirectional"))
      (node (ref "U1") (pin "24") (pinfunction "24_24") (pintype "bidirectional"))
    )
    (net (code "46") (name "Net-(TP20-1)") (class "Default")
      (node (ref "TP20") (pin "P$1") (pinfunction "1_P$1") (pintype "bidirectional"))
      (node (ref "U1") (pin "38") (pinfunction "38_38") (pintype "bidirectional"))
    )
    (net (code "47") (name "Net-(TP21-1)") (class "Default")
      (node (ref "TP21") (pin "P$1") (pinfunction "1_P$1") (pintype "bidirectional"))
      (node (ref "U1") (pin "37") (pinfunction "37_37") (pintype "bidirectional"))
    )
    (net (code "48") (name "Net-(TP22-1)") (class "Default")
      (node (ref "TP22") (pin "P$1") (pinfunction "1_P$1") (pintype "bidirectional"))
      (node (ref "U1") (pin "36") (pinfunction "36_36") (pintype "bidirectional"))
    )
    (net (code "49") (name "Net-(TP23-1)") (class "Default")
      (node (ref "TP23") (pin "P$1") (pinfunction "1_P$1") (pintype "bidirectional"))
      (node (ref "U1") (pin "35") (pinfunction "35_35") (pintype "bidirectional"))
    )
    (net (code "50") (name "Net-(TP27-1)") (class "Default")
      (node (ref "TP27") (pin "P$1") (pinfunction "1_P$1") (pintype "bidirectional"))
      (node (ref "U1") (pin "47") (pinfunction "47_47") (pintype "bidirectional"))
    )
    (net (code "51") (name "Net-(TP28-1)") (class "Default")
      (node (ref "TP28") (pin "P$1") (pinfunction "1_P$1") (pintype "bidirectional"))
      (node (ref "U1") (pin "48") (pinfunction "48_48") (pintype "bidirectional"))
    )
    (net (code "52") (name "Net-(Y1-1)") (class "Default")
      (node (ref "C20") (pin "1") (pinfunction "1_1") (pintype "passive"))
      (node (ref "U1") (pin "25") (pinfunction "25_25") (pintype "input"))
      (node (ref "Y1") (pin "P$1") (pinfunction "1_P$1") (pintype "passive"))
    )
    (net (code "53") (name "Net-(Y1-2)") (class "Default")
      (node (ref "C23") (pin "1") (pinfunction "1_1") (pintype "passive"))
      (node (ref "U1") (pin "26") (pinfunction "26_26") (pintype "output"))
      (node (ref "Y1") (pin "P$2") (pinfunction "2_P$2") (pintype "passive"))
    )
    (net (code "54") (name "RF_N") (class "Default")
      (node (ref "L1") (pin "P$2") (pinfunction "2_P$2") (pintype "passive"))
      (node (ref "U1") (pin "30") (pinfunction "30_30") (pintype "bidirectional"))
    )
    (net (code "55") (name "RF_P") (class "Default")
      (node (ref "L2") (pin "P$2") (pinfunction "2_P$2") (pintype "passive"))
      (node (ref "U1") (pin "29") (pinfunction "29_29") (pintype "bidirectional"))
    )
    (net (code "56") (name "VCC") (class "Default")
      (node (ref "C10") (pin "1") (pinfunction "1_1") (pintype "passive"))
      (node (ref "C12") (pin "1") (pinfunction "1_1") (pintype "passive"))
      (node (ref "C13") (pin "1") (pinfunction "1_1") (pintype "passive"))
      (node (ref "C16") (pin "1") (pinfunction "1_1") (pintype "passive"))
      (node (ref "C27") (pin "1") (pinfunction "1_1") (pintype "passive"))
      (node (ref "C32") (pin "1") (pinfunction "1_1") (pintype "passive"))
      (node (ref "L10") (pin "1") (pinfunction "1_1") (pintype "passive"))
      (node (ref "R1") (pin "2") (pinfunction "2_2") (pintype "passive"))
      (node (ref "R10") (pin "2") (pinfunction "2_2") (pintype "passive"))
      (node (ref "R11") (pin "2") (pinfunction "2_2") (pintype "passive"))
      (node (ref "R12") (pin "2") (pinfunction "2_2") (pintype "passive"))
      (node (ref "R8") (pin "2") (pinfunction "2_2") (pintype "passive"))
      (node (ref "R9") (pin "2") (pinfunction "2_2") (pintype "passive"))
      (node (ref "TP8") (pin "P$1") (pinfunction "1_P$1") (pintype "bidirectional"))
      (node (ref "U$1") (pin "2") (pinfunction "VCC_2") (pintype "power_in"))
      (node (ref "U$5") (pin "V+") (pinfunction "V+_V+") (pintype "passive"))
      (node (ref "U1") (pin "22") (pinfunction "22_22") (pintype "power_in"))
      (node (ref "U1") (pin "41") (pinfunction "41_41") (pintype "power_in"))
      (node (ref "U1") (pin "45") (pinfunction "45_45") (pintype "input"))
      (node (ref "U1") (pin "8") (pinfunction "8_8") (pintype "power_in"))
    )
    (net (code "57") (name "unconnected-(U1-Pad21)") (class "Default")
      (node (ref "U1") (pin "21") (pinfunction "21_21") (pintype "bidirectional"))
    )
    (net (code "58") (name "unconnected-(U1-Pad43)") (class "Default")
      (node (ref "U1") (pin "43") (pinfunction "43_43") (pintype "bidirectional"))
    )
    (net (code "59") (name "unconnected-(U1-Pad44)") (class "Default")
      (node (ref "U1") (pin "44") (pinfunction "44_44") (pintype "bidirectional"))
    )
    (net (code "60") (name "unconnected-(U1-Pad46)") (class "Default")
      (node (ref "U1") (pin "46") (pinfunction "46_46") (pintype "bidirectional"))
    )
    (net (code "61") (name "unconnected-(XCAL-DNI-Pad1)") (class "Default")
      (node (ref "XCAL-DNI") (pin "1") (pinfunction "1_1") (pintype "passive"))
    )
  )
)
